# Templates_CAN_bus.net
KiCad netlist of a schematic drawn in EAGLE
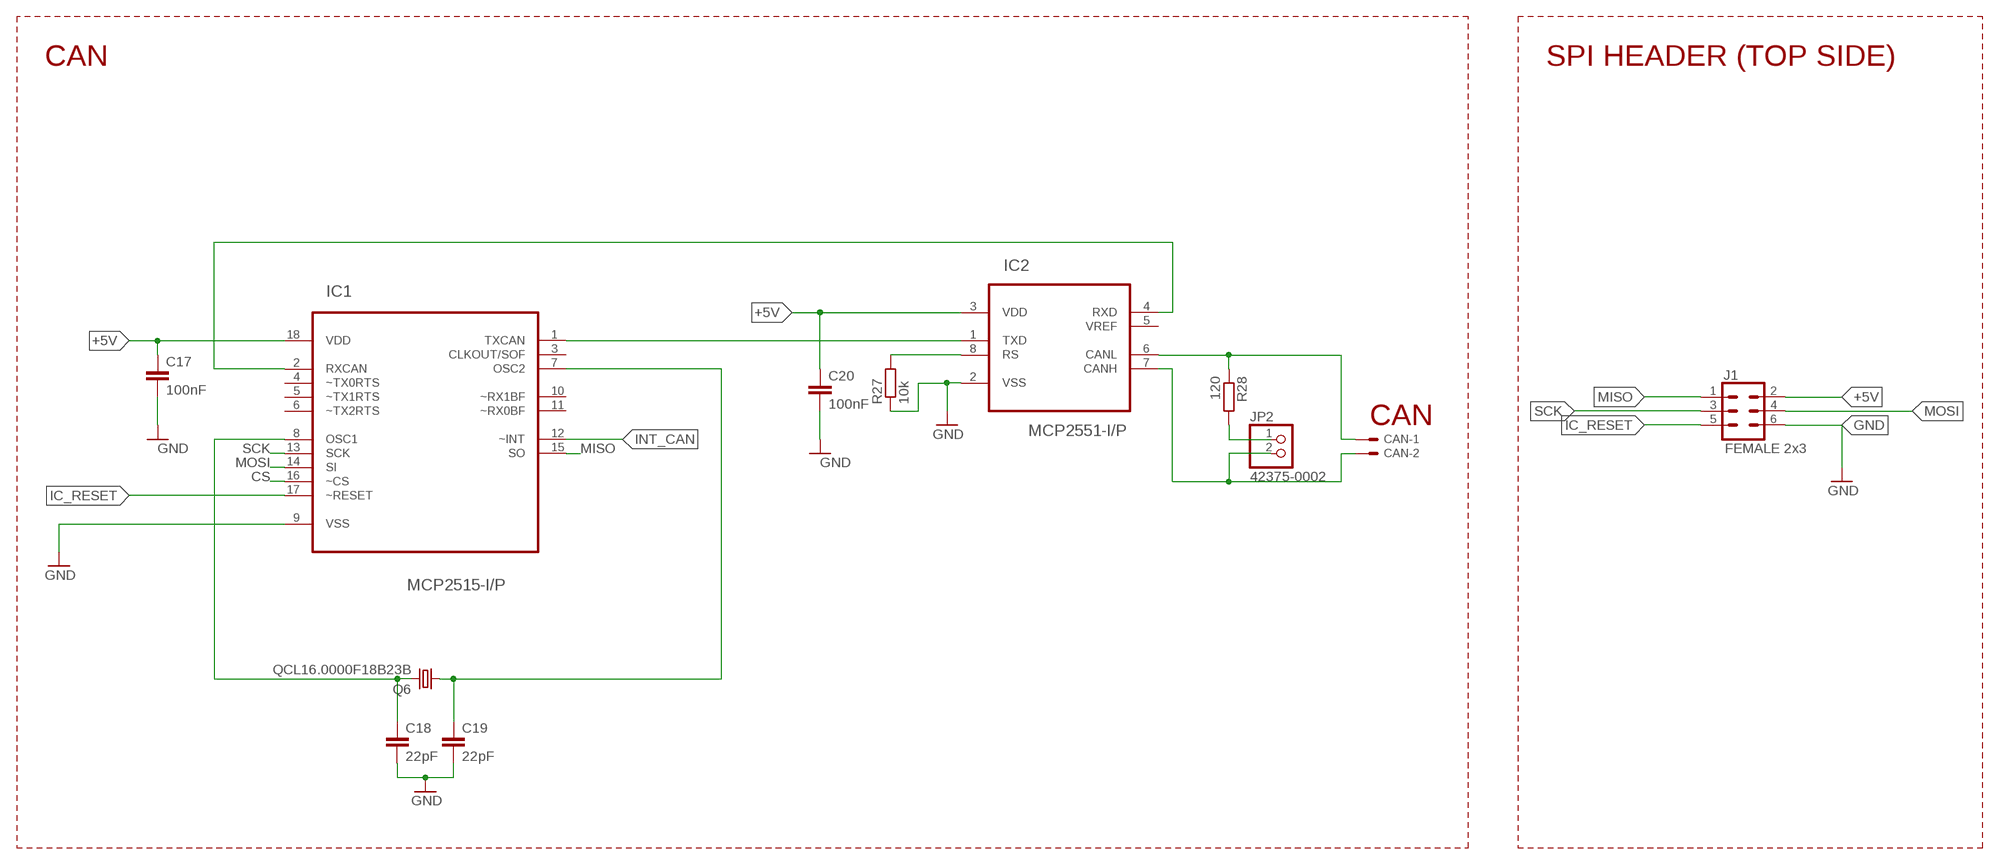
[diagram p0: schematic, sheet 1]

(export (version "E")
  (design (tool "Eeschema 10.0.6"))
  (components
    (comp (ref "C17")
      (value "100nF")
      (footprint "eagle-import:C025-025X050")
      (libsource (lib "eagle-import") (part "resistor_348_C-EU025-025X050"))
    )
    (comp (ref "C18")
      (value "22pF")
      (footprint "eagle-import:C050-024X044")
      (libsource (lib "eagle-import") (part "C-EU050-024X044"))
    )
    (comp (ref "C19")
      (value "22pF")
      (footprint "eagle-import:C050-024X044")
      (libsource (lib "eagle-import") (part "C-EU050-024X044"))
    )
    (comp (ref "C20")
      (value "100nF")
      (footprint "eagle-import:C025-025X050")
      (libsource (lib "eagle-import") (part "resistor_348_C-EU025-025X050"))
    )
    (comp (ref "CAN")
      (value "JST-XH-RIGHTANGLE-2-PIN-LONG-PAD")
      (footprint "eagle-import:JST-XH-RIGHTANGLE-2-PACKAGE-LONG-PAD")
      (libsource (lib "eagle-import") (part "JST-XH-RIGHTANGLE-2-PIN-LONG-PAD"))
    )
    (comp (ref "IC1")
      (value "MCP2515-I/P")
      (footprint "eagle-import:DIP254P762X432-18")
      (fields (field (name "MF") "Microchip"))
      (libsource (lib "eagle-import") (part "MCP2515-I/P"))
    )
    (comp (ref "IC2")
      (value "MCP2551-I/P")
      (footprint "eagle-import:DIP254P762X432-8")
      (fields (field (name "MF") "Microchip"))
      (libsource (lib "eagle-import") (part "MCP2551-I/P"))
    )
    (comp (ref "J1")
      (value "FEMALE 2x3")
      (footprint "eagle-import:2X3")
      (libsource (lib "eagle-import") (part "CONN_03X2FEMALE"))
    )
    (comp (ref "JP2")
      (value "42375-0002")
      (footprint "eagle-import:1X02")
      (libsource (lib "eagle-import") (part "PINHD-1X2"))
    )
    (comp (ref "Q6")
      (value "QCL16.0000F18B23B")
      (footprint "eagle-import:HC49_S")
      (libsource (lib "eagle-import") (part "CRYSTALHC49S"))
    )
    (comp (ref "R27")
      (value "10k")
      (footprint "eagle-import:0207_7")
      (libsource (lib "eagle-import") (part "R-EU_0207/7"))
    )
    (comp (ref "R28")
      (value "120")
      (footprint "eagle-import:0207_7")
      (libsource (lib "eagle-import") (part "R-EU_0207/7"))
    )
  )
  (nets
    (net (code "1") (name "+5V") (class "Default")
      (node (ref "C17") (pin "1") (pinfunction "1_1") (pintype "passive"))
      (node (ref "C20") (pin "1") (pinfunction "1_1") (pintype "passive"))
      (node (ref "IC1") (pin "18") (pinfunction "VDD_18") (pintype "power_in"))
      (node (ref "IC2") (pin "3") (pinfunction "VDD_3") (pintype "power_in"))
      (node (ref "J1") (pin "2") (pinfunction "2_2") (pintype "bidirectional"))
    )
    (net (code "2") (name "/CS") (class "Default")
      (node (ref "IC1") (pin "16") (pinfunction "~{CS}_16") (pintype "input"))
    )
    (net (code "3") (name "GND") (class "Default")
      (node (ref "C17") (pin "2") (pinfunction "2_2") (pintype "passive"))
      (node (ref "C18") (pin "2") (pinfunction "2_2") (pintype "passive"))
      (node (ref "C19") (pin "2") (pinfunction "2_2") (pintype "passive"))
      (node (ref "C20") (pin "2") (pinfunction "2_2") (pintype "passive"))
      (node (ref "IC1") (pin "9") (pinfunction "VSS_9") (pintype "power_in"))
      (node (ref "IC2") (pin "2") (pinfunction "VSS_2") (pintype "power_in"))
      (node (ref "J1") (pin "6") (pinfunction "6_6") (pintype "bidirectional"))
      (node (ref "R27") (pin "1") (pinfunction "1_1") (pintype "passive"))
    )
    (net (code "4") (name "IC_RESET") (class "Default")
      (node (ref "IC1") (pin "17") (pinfunction "~{RESET}_17") (pintype "input"))
      (node (ref "J1") (pin "5") (pinfunction "5_5") (pintype "bidirectional"))
    )
    (net (code "5") (name "INT_CAN") (class "Default")
      (node (ref "IC1") (pin "12") (pinfunction "~{INT}_12") (pintype "output"))
    )
    (net (code "6") (name "MISO") (class "Default")
      (node (ref "IC1") (pin "15") (pinfunction "SO_15") (pintype "output"))
      (node (ref "J1") (pin "1") (pinfunction "1_1") (pintype "bidirectional"))
    )
    (net (code "7") (name "MOSI") (class "Default")
      (node (ref "IC1") (pin "14") (pinfunction "SI_14") (pintype "input"))
      (node (ref "J1") (pin "4") (pinfunction "4_4") (pintype "bidirectional"))
    )
    (net (code "8") (name "Net-(CANA-S)") (class "Default")
      (node (ref "CAN") (pin "1") (pinfunction "S_1") (pintype "passive"))
      (node (ref "IC2") (pin "6") (pinfunction "CANL_6") (pintype "bidirectional"))
      (node (ref "R28") (pin "1") (pinfunction "1_1") (pintype "passive"))
    )
    (net (code "9") (name "Net-(CANB-S)") (class "Default")
      (node (ref "CAN") (pin "2") (pinfunction "S_2") (pintype "passive"))
      (node (ref "IC2") (pin "7") (pinfunction "CANH_7") (pintype "bidirectional"))
      (node (ref "JP2") (pin "2") (pinfunction "2_2") (pintype "passive"))
    )
    (net (code "10") (name "Net-(IC1-OSC1)") (class "Default")
      (node (ref "C18") (pin "1") (pinfunction "1_1") (pintype "passive"))
      (node (ref "IC1") (pin "8") (pinfunction "OSC1_8") (pintype "input"))
      (node (ref "Q6") (pin "2") (pinfunction "2_2") (pintype "passive"))
    )
    (net (code "11") (name "Net-(IC1-OSC2)") (class "Default")
      (node (ref "C19") (pin "1") (pinfunction "1_1") (pintype "passive"))
      (node (ref "IC1") (pin "7") (pinfunction "OSC2_7") (pintype "output"))
      (node (ref "Q6") (pin "1") (pinfunction "1_1") (pintype "passive"))
    )
    (net (code "12") (name "Net-(IC1-RXCAN)") (class "Default")
      (node (ref "IC1") (pin "2") (pinfunction "RXCAN_2") (pintype "input"))
      (node (ref "IC2") (pin "4") (pinfunction "RXD_4") (pintype "output"))
    )
    (net (code "13") (name "Net-(IC1-TXCAN)") (class "Default")
      (node (ref "IC1") (pin "1") (pinfunction "TXCAN_1") (pintype "output"))
      (node (ref "IC2") (pin "1") (pinfunction "TXD_1") (pintype "input"))
    )
    (net (code "14") (name "Net-(IC2-RS)") (class "Default")
      (node (ref "IC2") (pin "8") (pinfunction "RS_8") (pintype "input"))
      (node (ref "R27") (pin "2") (pinfunction "2_2") (pintype "passive"))
    )
    (net (code "15") (name "Net-(JP2-Pad1)") (class "Default")
      (node (ref "JP2") (pin "1") (pinfunction "1_1") (pintype "passive"))
      (node (ref "R28") (pin "2") (pinfunction "2_2") (pintype "passive"))
    )
    (net (code "16") (name "SCK") (class "Default")
      (node (ref "IC1") (pin "13") (pinfunction "SCK_13") (pintype "input"))
      (node (ref "J1") (pin "3") (pinfunction "3_3") (pintype "bidirectional"))
    )
    (net (code "17") (name "unconnected-(IC1-CLKOUT{slash}SOF-Pad3)") (class "Default")
      (node (ref "IC1") (pin "3") (pinfunction "CLKOUT/SOF_3") (pintype "output"))
    )
    (net (code "18") (name "unconnected-(IC1-~{RX0BF}-Pad11)") (class "Default")
      (node (ref "IC1") (pin "11") (pinfunction "~{RX0BF}_11") (pintype "output"))
    )
    (net (code "19") (name "unconnected-(IC1-~{RX1BF}-Pad10)") (class "Default")
      (node (ref "IC1") (pin "10") (pinfunction "~{RX1BF}_10") (pintype "output"))
    )
    (net (code "20") (name "unconnected-(IC1-~{TX0RTS}-Pad4)") (class "Default")
      (node (ref "IC1") (pin "4") (pinfunction "~{TX0RTS}_4") (pintype "input"))
    )
    (net (code "21") (name "unconnected-(IC1-~{TX1RTS}-Pad5)") (class "Default")
      (node (ref "IC1") (pin "5") (pinfunction "~{TX1RTS}_5") (pintype "input"))
    )
    (net (code "22") (name "unconnected-(IC1-~{TX2RTS}-Pad6)") (class "Default")
      (node (ref "IC1") (pin "6") (pinfunction "~{TX2RTS}_6") (pintype "input"))
    )
    (net (code "23") (name "unconnected-(IC2-VREF-Pad5)") (class "Default")
      (node (ref "IC2") (pin "5") (pinfunction "VREF_5") (pintype "output"))
    )
  )
)
